# RPi_SPI_outputs_uln_v02.net
KiCad netlist of a schematic drawn in EAGLE
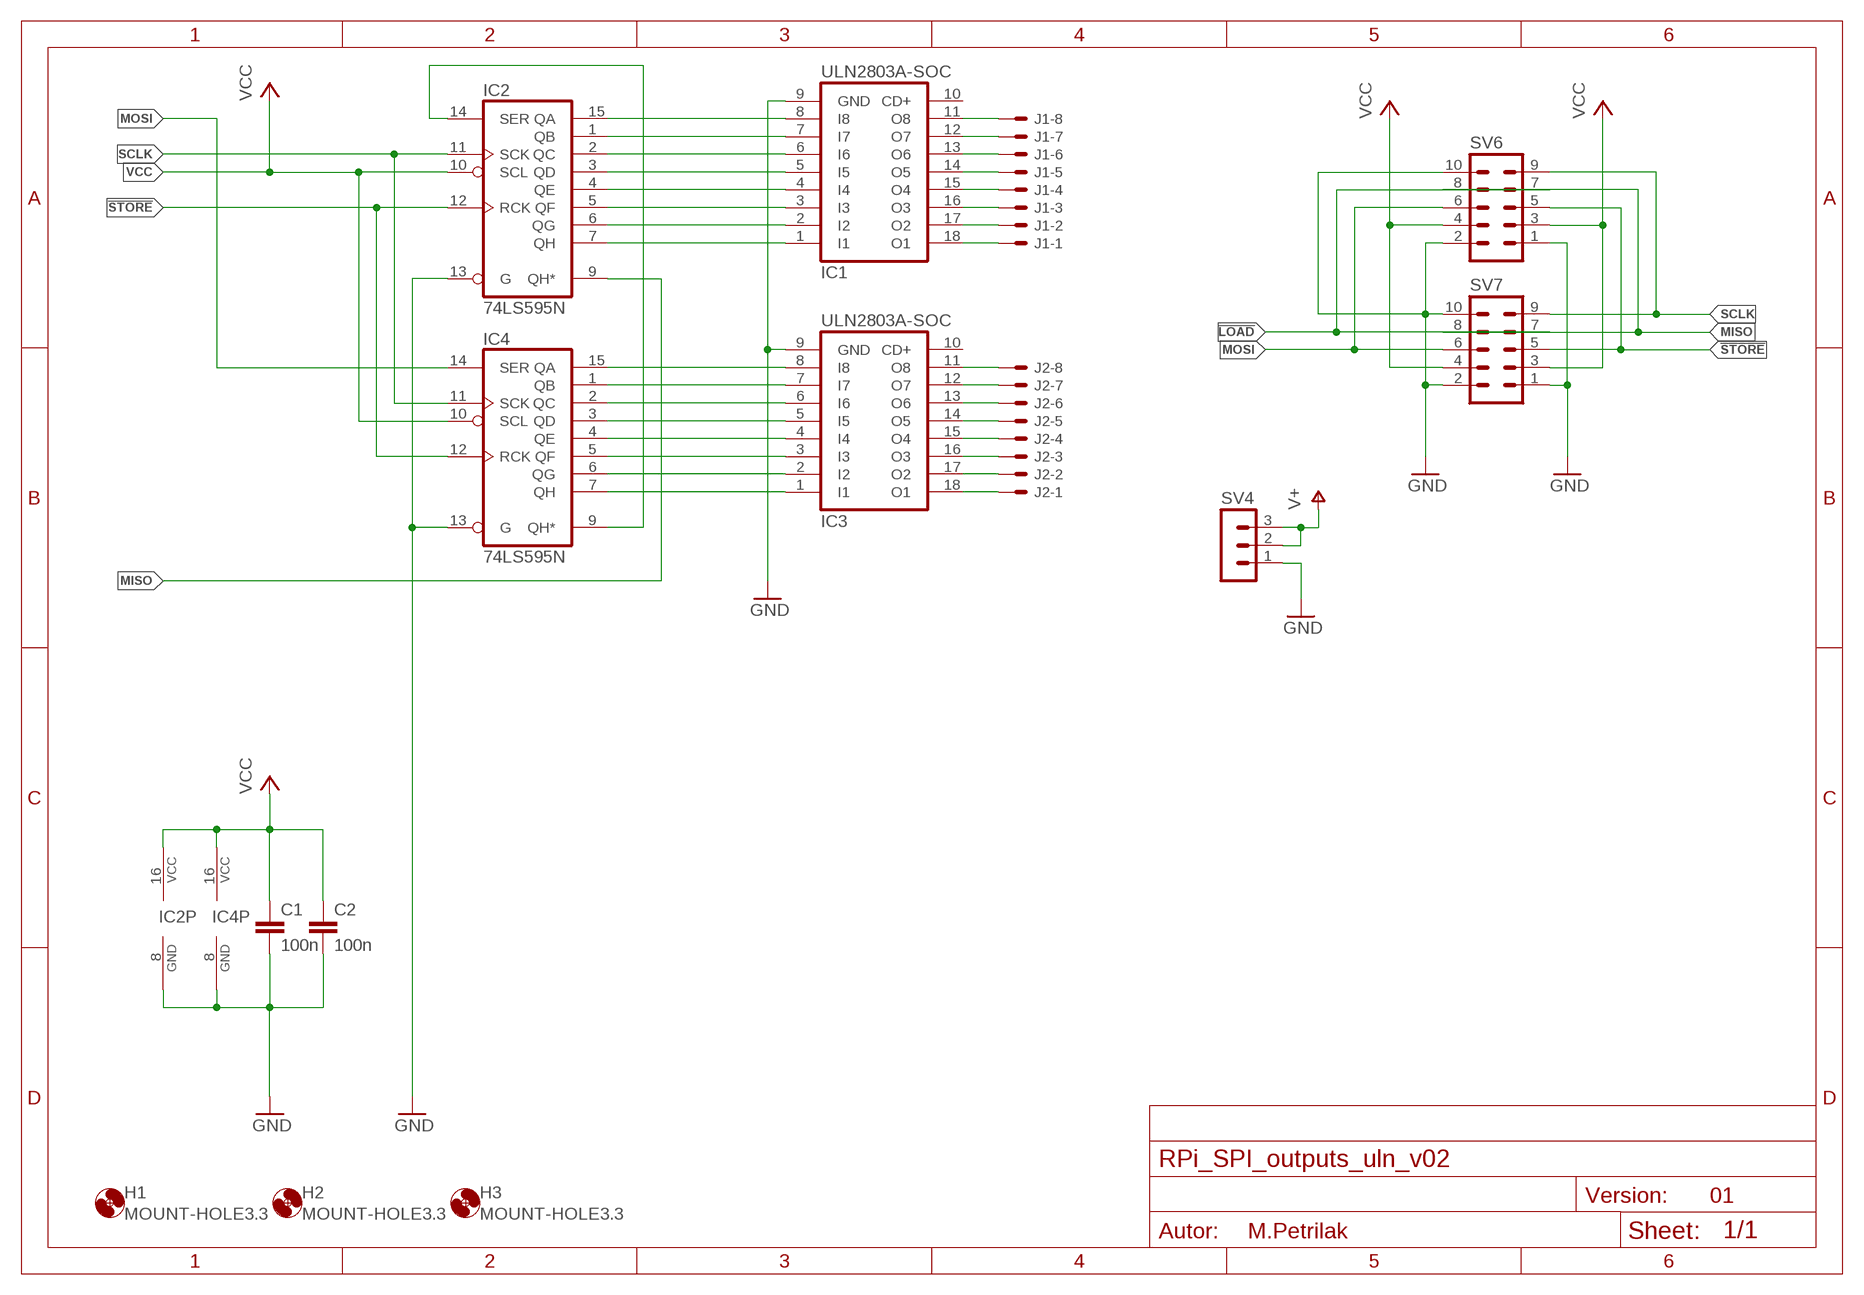
[diagram p0: schematic, sheet 1]

(export (version "E")
  (design (tool "Eeschema 10.0.6"))
  (components
    (comp (ref "C1")
      (value "100n")
      (footprint "eagle-import:C1206")
      (libsource (lib "eagle-import") (part "C-EUC1206"))
    )
    (comp (ref "C2")
      (value "100n")
      (footprint "eagle-import:C1206")
      (libsource (lib "eagle-import") (part "C-EUC1206"))
    )
    (comp (ref "H1")
      (value "MOUNT-HOLE3.3")
      (footprint "eagle-import:3,3")
      (libsource (lib "eagle-import") (part "MOUNT-HOLE3.3"))
    )
    (comp (ref "H2")
      (value "MOUNT-HOLE3.3")
      (footprint "eagle-import:3,3")
      (libsource (lib "eagle-import") (part "MOUNT-HOLE3.3"))
    )
    (comp (ref "H3")
      (value "MOUNT-HOLE3.3")
      (footprint "eagle-import:3,3")
      (libsource (lib "eagle-import") (part "MOUNT-HOLE3.3"))
    )
    (comp (ref "IC1")
      (value "ULN2803A-SOC")
      (footprint "eagle-import:SOCKET-18")
      (libsource (lib "eagle-import") (part "ULN2803A-SOC"))
    )
    (comp (ref "IC2")
      (value "74LS595N")
      (footprint "eagle-import:DIL16")
      (libsource (lib "eagle-import") (part "74595NLS"))
    )
    (comp (ref "IC3")
      (value "ULN2803A-SOC")
      (footprint "eagle-import:SOCKET-18")
      (libsource (lib "eagle-import") (part "ULN2803A-SOC"))
    )
    (comp (ref "IC4")
      (value "74LS595N")
      (footprint "eagle-import:DIL16")
      (libsource (lib "eagle-import") (part "74595NLS"))
    )
    (comp (ref "J1")
      (value "22-05-7088-SPEC-08")
      (footprint "eagle-import:7395-08_SPEC")
      (libsource (lib "eagle-import") (part "22-?-0805-7088-SPEC"))
    )
    (comp (ref "J2")
      (value "22-05-7088-SPEC-08")
      (footprint "eagle-import:7395-08_SPEC")
      (libsource (lib "eagle-import") (part "22-?-0805-7088-SPEC"))
    )
    (comp (ref "SV4")
      (value "MA03-1_NO")
      (footprint "eagle-import:MA03-1_NO")
      (libsource (lib "eagle-import") (part "MA03-1_NO"))
    )
    (comp (ref "SV6")
      (value "ML10")
      (footprint "eagle-import:ML10")
      (libsource (lib "eagle-import") (part "ML10"))
    )
    (comp (ref "SV7")
      (value "ML10")
      (footprint "eagle-import:ML10")
      (libsource (lib "eagle-import") (part "ML10"))
    )
  )
  (nets
    (net (code "1") (name "/~{LOAD}") (class "Default")
      (node (ref "SV6") (pin "7") (pinfunction "7_7") (pintype "passive"))
      (node (ref "SV7") (pin "7") (pinfunction "7_7") (pintype "passive"))
    )
    (net (code "2") (name "/~{STORE}") (class "Default")
      (node (ref "IC2") (pin "12") (pinfunction "RCK_12") (pintype "input"))
      (node (ref "IC4") (pin "12") (pinfunction "RCK_12") (pintype "input"))
      (node (ref "SV6") (pin "5") (pinfunction "5_5") (pintype "passive"))
      (node (ref "SV7") (pin "5") (pinfunction "5_5") (pintype "passive"))
    )
    (net (code "3") (name "GND") (class "Default")
      (node (ref "C1") (pin "2") (pinfunction "2_2") (pintype "passive"))
      (node (ref "C2") (pin "2") (pinfunction "2_2") (pintype "passive"))
      (node (ref "IC1") (pin "9") (pinfunction "GND_9") (pintype "power_in"))
      (node (ref "IC2") (pin "13") (pinfunction "G_13") (pintype "input"))
      (node (ref "IC2") (pin "8") (pinfunction "GND_8") (pintype "power_in"))
      (node (ref "IC3") (pin "9") (pinfunction "GND_9") (pintype "power_in"))
      (node (ref "IC4") (pin "13") (pinfunction "G_13") (pintype "input"))
      (node (ref "IC4") (pin "8") (pinfunction "GND_8") (pintype "power_in"))
      (node (ref "SV4") (pin "1") (pinfunction "1_1") (pintype "passive"))
      (node (ref "SV6") (pin "1") (pinfunction "1_1") (pintype "passive"))
      (node (ref "SV6") (pin "10") (pinfunction "10_10") (pintype "passive"))
      (node (ref "SV6") (pin "2") (pinfunction "2_2") (pintype "passive"))
      (node (ref "SV7") (pin "1") (pinfunction "1_1") (pintype "passive"))
      (node (ref "SV7") (pin "10") (pinfunction "10_10") (pintype "passive"))
      (node (ref "SV7") (pin "2") (pinfunction "2_2") (pintype "passive"))
    )
    (net (code "4") (name "MISO") (class "Default")
      (node (ref "IC2") (pin "9") (pinfunction "QH*_9") (pintype "tri_state"))
      (node (ref "SV6") (pin "8") (pinfunction "8_8") (pintype "passive"))
      (node (ref "SV7") (pin "8") (pinfunction "8_8") (pintype "passive"))
    )
    (net (code "5") (name "MOSI") (class "Default")
      (node (ref "IC4") (pin "14") (pinfunction "SER_14") (pintype "input"))
      (node (ref "SV6") (pin "6") (pinfunction "6_6") (pintype "passive"))
      (node (ref "SV7") (pin "6") (pinfunction "6_6") (pintype "passive"))
    )
    (net (code "6") (name "Net-(IC1-I1)") (class "Default")
      (node (ref "IC1") (pin "1") (pinfunction "I1_1") (pintype "input"))
      (node (ref "IC2") (pin "7") (pinfunction "QH_7") (pintype "tri_state"))
    )
    (net (code "7") (name "Net-(IC1-I2)") (class "Default")
      (node (ref "IC1") (pin "2") (pinfunction "I2_2") (pintype "input"))
      (node (ref "IC2") (pin "6") (pinfunction "QG_6") (pintype "tri_state"))
    )
    (net (code "8") (name "Net-(IC1-I3)") (class "Default")
      (node (ref "IC1") (pin "3") (pinfunction "I3_3") (pintype "input"))
      (node (ref "IC2") (pin "5") (pinfunction "QF_5") (pintype "tri_state"))
    )
    (net (code "9") (name "Net-(IC1-I4)") (class "Default")
      (node (ref "IC1") (pin "4") (pinfunction "I4_4") (pintype "input"))
      (node (ref "IC2") (pin "4") (pinfunction "QE_4") (pintype "tri_state"))
    )
    (net (code "10") (name "Net-(IC1-I5)") (class "Default")
      (node (ref "IC1") (pin "5") (pinfunction "I5_5") (pintype "input"))
      (node (ref "IC2") (pin "3") (pinfunction "QD_3") (pintype "tri_state"))
    )
    (net (code "11") (name "Net-(IC1-I6)") (class "Default")
      (node (ref "IC1") (pin "6") (pinfunction "I6_6") (pintype "input"))
      (node (ref "IC2") (pin "2") (pinfunction "QC_2") (pintype "tri_state"))
    )
    (net (code "12") (name "Net-(IC1-I7)") (class "Default")
      (node (ref "IC1") (pin "7") (pinfunction "I7_7") (pintype "input"))
      (node (ref "IC2") (pin "1") (pinfunction "QB_1") (pintype "tri_state"))
    )
    (net (code "13") (name "Net-(IC1-I8)") (class "Default")
      (node (ref "IC1") (pin "8") (pinfunction "I8_8") (pintype "input"))
      (node (ref "IC2") (pin "15") (pinfunction "QA_15") (pintype "tri_state"))
    )
    (net (code "14") (name "Net-(IC1-O1)") (class "Default")
      (node (ref "IC1") (pin "18") (pinfunction "O1_18") (pintype "open_collector"))
      (node (ref "J1") (pin "1") (pinfunction "S_1") (pintype "passive"))
    )
    (net (code "15") (name "Net-(IC1-O2)") (class "Default")
      (node (ref "IC1") (pin "17") (pinfunction "O2_17") (pintype "open_collector"))
      (node (ref "J1") (pin "2") (pinfunction "S_2") (pintype "passive"))
    )
    (net (code "16") (name "Net-(IC1-O3)") (class "Default")
      (node (ref "IC1") (pin "16") (pinfunction "O3_16") (pintype "open_collector"))
      (node (ref "J1") (pin "3") (pinfunction "S_3") (pintype "passive"))
    )
    (net (code "17") (name "Net-(IC1-O4)") (class "Default")
      (node (ref "IC1") (pin "15") (pinfunction "O4_15") (pintype "open_collector"))
      (node (ref "J1") (pin "4") (pinfunction "S_4") (pintype "passive"))
    )
    (net (code "18") (name "Net-(IC1-O5)") (class "Default")
      (node (ref "IC1") (pin "14") (pinfunction "O5_14") (pintype "open_collector"))
      (node (ref "J1") (pin "5") (pinfunction "S_5") (pintype "passive"))
    )
    (net (code "19") (name "Net-(IC1-O6)") (class "Default")
      (node (ref "IC1") (pin "13") (pinfunction "O6_13") (pintype "open_collector"))
      (node (ref "J1") (pin "6") (pinfunction "S_6") (pintype "passive"))
    )
    (net (code "20") (name "Net-(IC1-O7)") (class "Default")
      (node (ref "IC1") (pin "12") (pinfunction "O7_12") (pintype "open_collector"))
      (node (ref "J1") (pin "7") (pinfunction "S_7") (pintype "passive"))
    )
    (net (code "21") (name "Net-(IC1-O8)") (class "Default")
      (node (ref "IC1") (pin "11") (pinfunction "O8_11") (pintype "open_collector"))
      (node (ref "J1") (pin "8") (pinfunction "S_8") (pintype "passive"))
    )
    (net (code "22") (name "Net-(IC2A-SER)") (class "Default")
      (node (ref "IC2") (pin "14") (pinfunction "SER_14") (pintype "input"))
      (node (ref "IC4") (pin "9") (pinfunction "QH*_9") (pintype "tri_state"))
    )
    (net (code "23") (name "Net-(IC3-I1)") (class "Default")
      (node (ref "IC3") (pin "1") (pinfunction "I1_1") (pintype "input"))
      (node (ref "IC4") (pin "7") (pinfunction "QH_7") (pintype "tri_state"))
    )
    (net (code "24") (name "Net-(IC3-I2)") (class "Default")
      (node (ref "IC3") (pin "2") (pinfunction "I2_2") (pintype "input"))
      (node (ref "IC4") (pin "6") (pinfunction "QG_6") (pintype "tri_state"))
    )
    (net (code "25") (name "Net-(IC3-I3)") (class "Default")
      (node (ref "IC3") (pin "3") (pinfunction "I3_3") (pintype "input"))
      (node (ref "IC4") (pin "5") (pinfunction "QF_5") (pintype "tri_state"))
    )
    (net (code "26") (name "Net-(IC3-I4)") (class "Default")
      (node (ref "IC3") (pin "4") (pinfunction "I4_4") (pintype "input"))
      (node (ref "IC4") (pin "4") (pinfunction "QE_4") (pintype "tri_state"))
    )
    (net (code "27") (name "Net-(IC3-I5)") (class "Default")
      (node (ref "IC3") (pin "5") (pinfunction "I5_5") (pintype "input"))
      (node (ref "IC4") (pin "3") (pinfunction "QD_3") (pintype "tri_state"))
    )
    (net (code "28") (name "Net-(IC3-I6)") (class "Default")
      (node (ref "IC3") (pin "6") (pinfunction "I6_6") (pintype "input"))
      (node (ref "IC4") (pin "2") (pinfunction "QC_2") (pintype "tri_state"))
    )
    (net (code "29") (name "Net-(IC3-I7)") (class "Default")
      (node (ref "IC3") (pin "7") (pinfunction "I7_7") (pintype "input"))
      (node (ref "IC4") (pin "1") (pinfunction "QB_1") (pintype "tri_state"))
    )
    (net (code "30") (name "Net-(IC3-I8)") (class "Default")
      (node (ref "IC3") (pin "8") (pinfunction "I8_8") (pintype "input"))
      (node (ref "IC4") (pin "15") (pinfunction "QA_15") (pintype "tri_state"))
    )
    (net (code "31") (name "Net-(IC3-O1)") (class "Default")
      (node (ref "IC3") (pin "18") (pinfunction "O1_18") (pintype "open_collector"))
      (node (ref "J2") (pin "1") (pinfunction "S_1") (pintype "passive"))
    )
    (net (code "32") (name "Net-(IC3-O2)") (class "Default")
      (node (ref "IC3") (pin "17") (pinfunction "O2_17") (pintype "open_collector"))
      (node (ref "J2") (pin "2") (pinfunction "S_2") (pintype "passive"))
    )
    (net (code "33") (name "Net-(IC3-O3)") (class "Default")
      (node (ref "IC3") (pin "16") (pinfunction "O3_16") (pintype "open_collector"))
      (node (ref "J2") (pin "3") (pinfunction "S_3") (pintype "passive"))
    )
    (net (code "34") (name "Net-(IC3-O4)") (class "Default")
      (node (ref "IC3") (pin "15") (pinfunction "O4_15") (pintype "open_collector"))
      (node (ref "J2") (pin "4") (pinfunction "S_4") (pintype "passive"))
    )
    (net (code "35") (name "Net-(IC3-O5)") (class "Default")
      (node (ref "IC3") (pin "14") (pinfunction "O5_14") (pintype "open_collector"))
      (node (ref "J2") (pin "5") (pinfunction "S_5") (pintype "passive"))
    )
    (net (code "36") (name "Net-(IC3-O6)") (class "Default")
      (node (ref "IC3") (pin "13") (pinfunction "O6_13") (pintype "open_collector"))
      (node (ref "J2") (pin "6") (pinfunction "S_6") (pintype "passive"))
    )
    (net (code "37") (name "Net-(IC3-O7)") (class "Default")
      (node (ref "IC3") (pin "12") (pinfunction "O7_12") (pintype "open_collector"))
      (node (ref "J2") (pin "7") (pinfunction "S_7") (pintype "passive"))
    )
    (net (code "38") (name "Net-(IC3-O8)") (class "Default")
      (node (ref "IC3") (pin "11") (pinfunction "O8_11") (pintype "open_collector"))
      (node (ref "J2") (pin "8") (pinfunction "S_8") (pintype "passive"))
    )
    (net (code "39") (name "SCLK") (class "Default")
      (node (ref "IC2") (pin "11") (pinfunction "SCK_11") (pintype "input"))
      (node (ref "IC4") (pin "11") (pinfunction "SCK_11") (pintype "input"))
      (node (ref "SV6") (pin "9") (pinfunction "9_9") (pintype "passive"))
      (node (ref "SV7") (pin "9") (pinfunction "9_9") (pintype "passive"))
    )
    (net (code "40") (name "V+") (class "Default")
      (node (ref "SV4") (pin "2") (pinfunction "2_2") (pintype "passive"))
      (node (ref "SV4") (pin "3") (pinfunction "3_3") (pintype "passive"))
    )
    (net (code "41") (name "VCC") (class "Default")
      (node (ref "C1") (pin "1") (pinfunction "1_1") (pintype "passive"))
      (node (ref "C2") (pin "1") (pinfunction "1_1") (pintype "passive"))
      (node (ref "IC2") (pin "10") (pinfunction "SCL_10") (pintype "input"))
      (node (ref "IC2") (pin "16") (pinfunction "VCC_16") (pintype "power_in"))
      (node (ref "IC4") (pin "10") (pinfunction "SCL_10") (pintype "input"))
      (node (ref "IC4") (pin "16") (pinfunction "VCC_16") (pintype "power_in"))
      (node (ref "SV6") (pin "3") (pinfunction "3_3") (pintype "passive"))
      (node (ref "SV6") (pin "4") (pinfunction "4_4") (pintype "passive"))
      (node (ref "SV7") (pin "3") (pinfunction "3_3") (pintype "passive"))
      (node (ref "SV7") (pin "4") (pinfunction "4_4") (pintype "passive"))
    )
    (net (code "42") (name "unconnected-(IC1-CD+-Pad10)") (class "Default")
      (node (ref "IC1") (pin "10") (pinfunction "CD+_10") (pintype "passive"))
    )
    (net (code "43") (name "unconnected-(IC3-CD+-Pad10)") (class "Default")
      (node (ref "IC3") (pin "10") (pinfunction "CD+_10") (pintype "passive"))
    )
  )
)
